# PCB.net
KiCad netlist of a schematic drawn in EAGLE
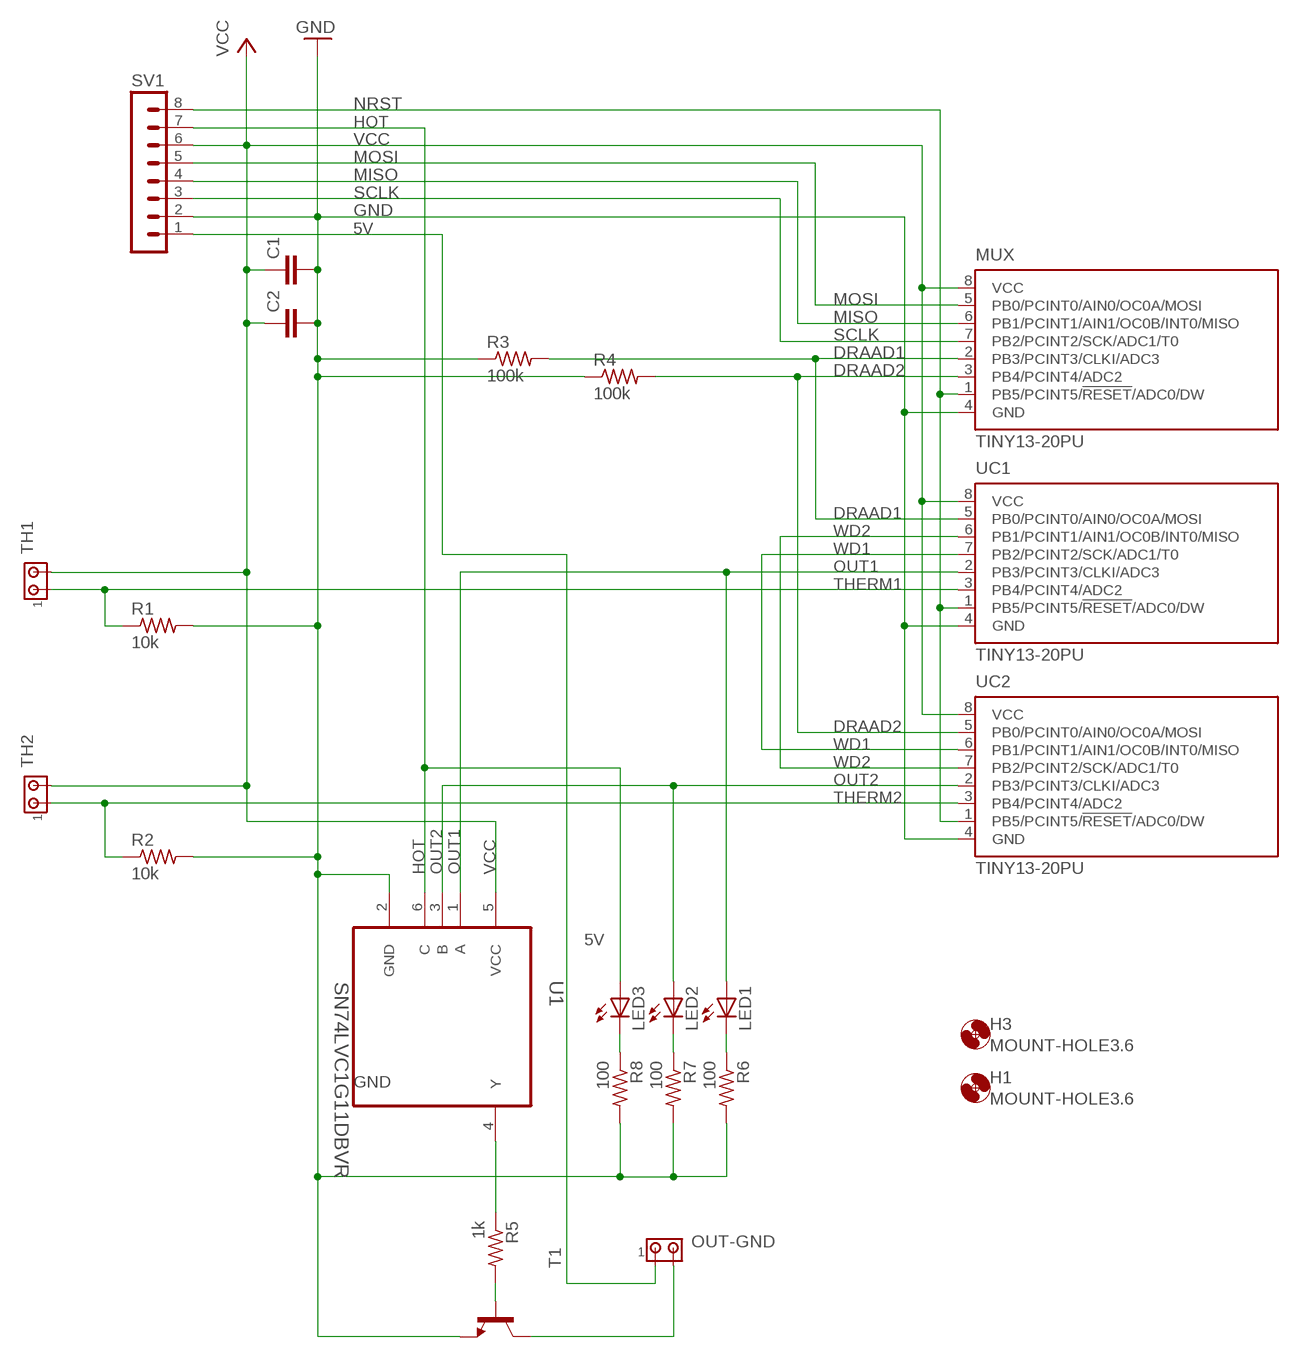
[diagram p0: schematic, sheet 1]

(export (version "E")
  (design (tool "Eeschema 10.0.6"))
  (components
    (comp (ref "C1")
      (value "C2.5/2")
      (footprint "eagle-import:C2.5-2")
      (libsource (lib "eagle-import") (part "C2.5/2"))
    )
    (comp (ref "C2")
      (value "C2.5/2")
      (footprint "eagle-import:C2.5-2")
      (libsource (lib "eagle-import") (part "C2.5/2"))
    )
    (comp (ref "H1")
      (value "MOUNT-HOLE3.6")
      (footprint "eagle-import:3,6")
      (libsource (lib "eagle-import") (part "MOUNT-HOLE3.6"))
    )
    (comp (ref "H3")
      (value "MOUNT-HOLE3.6")
      (footprint "eagle-import:3,6")
      (libsource (lib "eagle-import") (part "MOUNT-HOLE3.6"))
    )
    (comp (ref "LED1")
      (value "LEDSML0805")
      (footprint "eagle-import:SML0805")
      (libsource (lib "eagle-import") (part "LEDSML0805"))
    )
    (comp (ref "LED2")
      (value "LEDSML0805")
      (footprint "eagle-import:SML0805")
      (libsource (lib "eagle-import") (part "LEDSML0805"))
    )
    (comp (ref "LED3")
      (value "LEDSML0805")
      (footprint "eagle-import:SML0805")
      (libsource (lib "eagle-import") (part "LEDSML0805"))
    )
    (comp (ref "MUX")
      (value "TINY13-20PU")
      (footprint "eagle-import:DIL08")
      (fields (field (name "MPN") "ATTINY13-20PU"))
      (libsource (lib "eagle-import") (part "TINY13PU-20"))
    )
    (comp (ref "OUT-GND")
      (value "MTA02-100")
      (footprint "eagle-import:10X02MTA")
      (libsource (lib "eagle-import") (part "MTA02-100"))
    )
    (comp (ref "R1")
      (value "10k")
      (footprint "eagle-import:R0805")
      (libsource (lib "eagle-import") (part "R-US_R0805"))
    )
    (comp (ref "R2")
      (value "10k")
      (footprint "eagle-import:R0805")
      (libsource (lib "eagle-import") (part "R-US_R0805"))
    )
    (comp (ref "R3")
      (value "100k")
      (footprint "eagle-import:R0805")
      (libsource (lib "eagle-import") (part "R-US_R0805"))
    )
    (comp (ref "R4")
      (value "100k")
      (footprint "eagle-import:R0805")
      (libsource (lib "eagle-import") (part "R-US_R0805"))
    )
    (comp (ref "R5")
      (value "1k")
      (footprint "eagle-import:R0805")
      (libsource (lib "eagle-import") (part "R-US_R0805"))
    )
    (comp (ref "R6")
      (value "100")
      (footprint "eagle-import:R0805")
      (libsource (lib "eagle-import") (part "R-US_R0805"))
    )
    (comp (ref "R7")
      (value "100")
      (footprint "eagle-import:R0805")
      (libsource (lib "eagle-import") (part "R-US_R0805"))
    )
    (comp (ref "R8")
      (value "100")
      (footprint "eagle-import:R0805")
      (libsource (lib "eagle-import") (part "R-US_R0805"))
    )
    (comp (ref "SV1")
      (value "MA08-1")
      (footprint "eagle-import:MA08-1")
      (libsource (lib "eagle-import") (part "MA08-1"))
    )
    (comp (ref "T1")
      (value "-NPN-TO126V")
      (footprint "eagle-import:TO126V")
      (libsource (lib "eagle-import") (part "-NPN-TO126V"))
    )
    (comp (ref "TH1")
      (value "MTA02-100")
      (footprint "eagle-import:10X02MTA")
      (libsource (lib "eagle-import") (part "MTA02-100"))
    )
    (comp (ref "TH2")
      (value "MTA02-100")
      (footprint "eagle-import:10X02MTA")
      (libsource (lib "eagle-import") (part "MTA02-100"))
    )
    (comp (ref "U1")
      (value "SN74LVC1G11DBVR")
      (footprint "eagle-import:SOT95P280X145-6N")
      (libsource (lib "eagle-import") (part "SN74LVC1G11DBVR"))
    )
    (comp (ref "UC1")
      (value "TINY13-20PU")
      (footprint "eagle-import:DIL08")
      (fields (field (name "MPN") "ATTINY13-20PU"))
      (libsource (lib "eagle-import") (part "TINY13PU-20"))
    )
    (comp (ref "UC2")
      (value "TINY13-20PU")
      (footprint "eagle-import:DIL08")
      (fields (field (name "MPN") "ATTINY13-20PU"))
      (libsource (lib "eagle-import") (part "TINY13PU-20"))
    )
  )
  (nets
    (net (code "1") (name "/5V") (class "Default")
      (node (ref "OUT-GND") (pin "1") (pinfunction "1_1") (pintype "passive"))
      (node (ref "SV1") (pin "1") (pinfunction "1_1") (pintype "passive"))
    )
    (net (code "2") (name "/DRAAD1") (class "Default")
      (node (ref "MUX") (pin "2") (pinfunction "PB3/PCINT3/CLKI/ADC3_2") (pintype "bidirectional"))
      (node (ref "R3") (pin "2") (pinfunction "2_2") (pintype "passive"))
      (node (ref "UC1") (pin "5") (pinfunction "PB0/PCINT0/AIN0/OC0A/MOSI_5") (pintype "bidirectional"))
    )
    (net (code "3") (name "/DRAAD2") (class "Default")
      (node (ref "MUX") (pin "3") (pinfunction "PB4/PCINT4/ADC2_3") (pintype "bidirectional"))
      (node (ref "R4") (pin "2") (pinfunction "2_2") (pintype "passive"))
      (node (ref "UC2") (pin "5") (pinfunction "PB0/PCINT0/AIN0/OC0A/MOSI_5") (pintype "bidirectional"))
    )
    (net (code "4") (name "/HOT") (class "Default")
      (node (ref "LED3") (pin "A") (pinfunction "A_A") (pintype "passive"))
      (node (ref "SV1") (pin "7") (pinfunction "7_7") (pintype "passive"))
      (node (ref "U1") (pin "6") (pinfunction "C_6") (pintype "input"))
    )
    (net (code "5") (name "/MISO") (class "Default")
      (node (ref "MUX") (pin "6") (pinfunction "PB1/PCINT1/AIN1/OC0B/INT0/MISO_6") (pintype "bidirectional"))
      (node (ref "SV1") (pin "4") (pinfunction "4_4") (pintype "passive"))
    )
    (net (code "6") (name "/MOSI") (class "Default")
      (node (ref "MUX") (pin "5") (pinfunction "PB0/PCINT0/AIN0/OC0A/MOSI_5") (pintype "bidirectional"))
      (node (ref "SV1") (pin "5") (pinfunction "5_5") (pintype "passive"))
    )
    (net (code "7") (name "/NRST") (class "Default")
      (node (ref "MUX") (pin "1") (pinfunction "PB5/PCINT5/~{RESET}/ADC0/DW_1") (pintype "bidirectional"))
      (node (ref "SV1") (pin "8") (pinfunction "8_8") (pintype "passive"))
      (node (ref "UC1") (pin "1") (pinfunction "PB5/PCINT5/~{RESET}/ADC0/DW_1") (pintype "bidirectional"))
      (node (ref "UC2") (pin "1") (pinfunction "PB5/PCINT5/~{RESET}/ADC0/DW_1") (pintype "bidirectional"))
    )
    (net (code "8") (name "/OUT1") (class "Default")
      (node (ref "LED1") (pin "A") (pinfunction "A_A") (pintype "passive"))
      (node (ref "U1") (pin "1") (pinfunction "A_1") (pintype "input"))
      (node (ref "UC1") (pin "2") (pinfunction "PB3/PCINT3/CLKI/ADC3_2") (pintype "bidirectional"))
    )
    (net (code "9") (name "/OUT2") (class "Default")
      (node (ref "LED2") (pin "A") (pinfunction "A_A") (pintype "passive"))
      (node (ref "U1") (pin "3") (pinfunction "B_3") (pintype "input"))
      (node (ref "UC2") (pin "2") (pinfunction "PB3/PCINT3/CLKI/ADC3_2") (pintype "bidirectional"))
    )
    (net (code "10") (name "/SCLK") (class "Default")
      (node (ref "MUX") (pin "7") (pinfunction "PB2/PCINT2/SCK/ADC1/T0_7") (pintype "bidirectional"))
      (node (ref "SV1") (pin "3") (pinfunction "3_3") (pintype "passive"))
    )
    (net (code "11") (name "/THERM1") (class "Default")
      (node (ref "R1") (pin "1") (pinfunction "1_1") (pintype "passive"))
      (node (ref "TH1") (pin "1") (pinfunction "1_1") (pintype "passive"))
      (node (ref "UC1") (pin "3") (pinfunction "PB4/PCINT4/ADC2_3") (pintype "bidirectional"))
    )
    (net (code "12") (name "/THERM2") (class "Default")
      (node (ref "R2") (pin "1") (pinfunction "1_1") (pintype "passive"))
      (node (ref "TH2") (pin "1") (pinfunction "1_1") (pintype "passive"))
      (node (ref "UC2") (pin "3") (pinfunction "PB4/PCINT4/ADC2_3") (pintype "bidirectional"))
    )
    (net (code "13") (name "/WD1") (class "Default")
      (node (ref "UC1") (pin "7") (pinfunction "PB2/PCINT2/SCK/ADC1/T0_7") (pintype "bidirectional"))
      (node (ref "UC2") (pin "6") (pinfunction "PB1/PCINT1/AIN1/OC0B/INT0/MISO_6") (pintype "bidirectional"))
    )
    (net (code "14") (name "/WD2") (class "Default")
      (node (ref "UC1") (pin "6") (pinfunction "PB1/PCINT1/AIN1/OC0B/INT0/MISO_6") (pintype "bidirectional"))
      (node (ref "UC2") (pin "7") (pinfunction "PB2/PCINT2/SCK/ADC1/T0_7") (pintype "bidirectional"))
    )
    (net (code "15") (name "GND") (class "Default")
      (node (ref "C1") (pin "2") (pinfunction "2_2") (pintype "passive"))
      (node (ref "C2") (pin "2") (pinfunction "2_2") (pintype "passive"))
      (node (ref "MUX") (pin "4") (pinfunction "GND_4") (pintype "power_in"))
      (node (ref "R1") (pin "2") (pinfunction "2_2") (pintype "passive"))
      (node (ref "R2") (pin "2") (pinfunction "2_2") (pintype "passive"))
      (node (ref "R3") (pin "1") (pinfunction "1_1") (pintype "passive"))
      (node (ref "R4") (pin "1") (pinfunction "1_1") (pintype "passive"))
      (node (ref "R6") (pin "2") (pinfunction "2_2") (pintype "passive"))
      (node (ref "R7") (pin "2") (pinfunction "2_2") (pintype "passive"))
      (node (ref "R8") (pin "2") (pinfunction "2_2") (pintype "passive"))
      (node (ref "SV1") (pin "2") (pinfunction "2_2") (pintype "passive"))
      (node (ref "T1") (pin "1") (pinfunction "E_1") (pintype "passive"))
      (node (ref "U1") (pin "2") (pinfunction "GND_2") (pintype "passive"))
      (node (ref "UC1") (pin "4") (pinfunction "GND_4") (pintype "power_in"))
      (node (ref "UC2") (pin "4") (pinfunction "GND_4") (pintype "power_in"))
    )
    (net (code "16") (name "Net-(LED1-PadC)") (class "Default")
      (node (ref "LED1") (pin "C") (pinfunction "C_C") (pintype "passive"))
      (node (ref "R6") (pin "1") (pinfunction "1_1") (pintype "passive"))
    )
    (net (code "17") (name "Net-(LED2-PadC)") (class "Default")
      (node (ref "LED2") (pin "C") (pinfunction "C_C") (pintype "passive"))
      (node (ref "R7") (pin "1") (pinfunction "1_1") (pintype "passive"))
    )
    (net (code "18") (name "Net-(LED3-PadC)") (class "Default")
      (node (ref "LED3") (pin "C") (pinfunction "C_C") (pintype "passive"))
      (node (ref "R8") (pin "1") (pinfunction "1_1") (pintype "passive"))
    )
    (net (code "19") (name "Net-(T1-B)") (class "Default")
      (node (ref "R5") (pin "2") (pinfunction "2_2") (pintype "passive"))
      (node (ref "T1") (pin "3") (pinfunction "B_3") (pintype "passive"))
    )
    (net (code "20") (name "Net-(T1-C)") (class "Default")
      (node (ref "OUT-GND") (pin "2") (pinfunction "2_2") (pintype "passive"))
      (node (ref "T1") (pin "2") (pinfunction "C_2") (pintype "passive"))
    )
    (net (code "21") (name "Net-(U1-Y)") (class "Default")
      (node (ref "R5") (pin "1") (pinfunction "1_1") (pintype "passive"))
      (node (ref "U1") (pin "4") (pinfunction "Y_4") (pintype "output"))
    )
    (net (code "22") (name "VCC") (class "Default")
      (node (ref "C1") (pin "1") (pinfunction "1_1") (pintype "passive"))
      (node (ref "C2") (pin "1") (pinfunction "1_1") (pintype "passive"))
      (node (ref "MUX") (pin "8") (pinfunction "VCC_8") (pintype "power_in"))
      (node (ref "SV1") (pin "6") (pinfunction "6_6") (pintype "passive"))
      (node (ref "TH1") (pin "2") (pinfunction "2_2") (pintype "passive"))
      (node (ref "TH2") (pin "2") (pinfunction "2_2") (pintype "passive"))
      (node (ref "U1") (pin "5") (pinfunction "VCC_5") (pintype "power_in"))
      (node (ref "UC1") (pin "8") (pinfunction "VCC_8") (pintype "power_in"))
      (node (ref "UC2") (pin "8") (pinfunction "VCC_8") (pintype "power_in"))
    )
  )
)
